# car.net
KiCad netlist of a schematic drawn in EAGLE
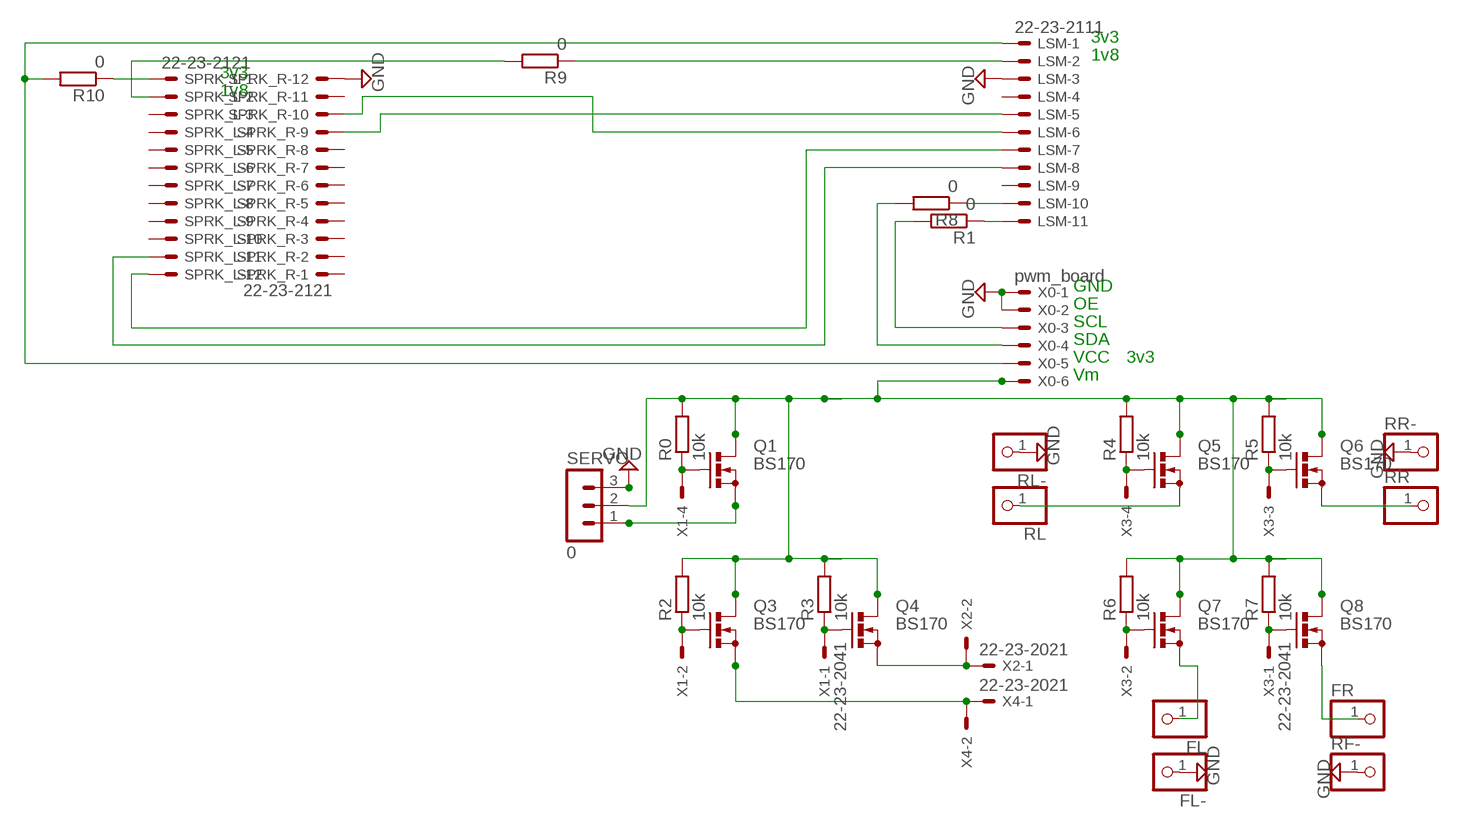
[diagram p0: schematic, sheet 1]

(export (version "E")
  (design (tool "Eeschema 10.0.6"))
  (components
    (comp (ref "FL")
      (value "PINHD-1X1")
      (footprint "eagle-import:1X01")
      (libsource (lib "eagle-import") (part "PINHD-1X1"))
    )
    (comp (ref "FL-")
      (value "PINHD-1X1")
      (footprint "eagle-import:1X01")
      (libsource (lib "eagle-import") (part "PINHD-1X1"))
    )
    (comp (ref "FR")
      (value "PINHD-1X1")
      (footprint "eagle-import:1X01")
      (libsource (lib "eagle-import") (part "PINHD-1X1"))
    )
    (comp (ref "LSM")
      (value "22-23-2111")
      (footprint "eagle-import:22-23-2111")
      (fields (field (name "MF") "MOLEX"))
      (libsource (lib "eagle-import") (part "22-23-2111"))
    )
    (comp (ref "Q1")
      (value "BS170")
      (footprint "eagle-import:SOT54E")
      (libsource (lib "eagle-import") (part "BS170"))
    )
    (comp (ref "Q3")
      (value "BS170")
      (footprint "eagle-import:SOT54E")
      (libsource (lib "eagle-import") (part "BS170"))
    )
    (comp (ref "Q4")
      (value "BS170")
      (footprint "eagle-import:SOT54E")
      (libsource (lib "eagle-import") (part "BS170"))
    )
    (comp (ref "Q5")
      (value "BS170")
      (footprint "eagle-import:SOT54E")
      (libsource (lib "eagle-import") (part "BS170"))
    )
    (comp (ref "Q6")
      (value "BS170")
      (footprint "eagle-import:SOT54E")
      (libsource (lib "eagle-import") (part "BS170"))
    )
    (comp (ref "Q7")
      (value "BS170")
      (footprint "eagle-import:SOT54E")
      (libsource (lib "eagle-import") (part "BS170"))
    )
    (comp (ref "Q8")
      (value "BS170")
      (footprint "eagle-import:SOT54E")
      (libsource (lib "eagle-import") (part "BS170"))
    )
    (comp (ref "R0")
      (value "10k")
      (footprint "eagle-import:0207_10")
      (libsource (lib "eagle-import") (part "R-EU_0207/10"))
    )
    (comp (ref "R1")
      (value "0")
      (footprint "eagle-import:0207_10")
      (libsource (lib "eagle-import") (part "R-EU_0207/10"))
    )
    (comp (ref "R2")
      (value "10k")
      (footprint "eagle-import:0207_10")
      (libsource (lib "eagle-import") (part "R-EU_0207/10"))
    )
    (comp (ref "R3")
      (value "10k")
      (footprint "eagle-import:0207_10")
      (libsource (lib "eagle-import") (part "R-EU_0207/10"))
    )
    (comp (ref "R4")
      (value "10k")
      (footprint "eagle-import:0207_10")
      (libsource (lib "eagle-import") (part "R-EU_0207/10"))
    )
    (comp (ref "R5")
      (value "10k")
      (footprint "eagle-import:0207_10")
      (libsource (lib "eagle-import") (part "R-EU_0207/10"))
    )
    (comp (ref "R6")
      (value "10k")
      (footprint "eagle-import:0207_10")
      (libsource (lib "eagle-import") (part "R-EU_0207/10"))
    )
    (comp (ref "R7")
      (value "10k")
      (footprint "eagle-import:0207_10")
      (libsource (lib "eagle-import") (part "R-EU_0207/10"))
    )
    (comp (ref "R8")
      (value "0")
      (footprint "eagle-import:0207_10")
      (libsource (lib "eagle-import") (part "R-EU_0207/10"))
    )
    (comp (ref "R9")
      (value "0")
      (footprint "eagle-import:0207_10")
      (libsource (lib "eagle-import") (part "R-EU_0207/10"))
    )
    (comp (ref "R10")
      (value "0")
      (footprint "eagle-import:0207_10")
      (libsource (lib "eagle-import") (part "R-EU_0207/10"))
    )
    (comp (ref "RF-")
      (value "PINHD-1X1")
      (footprint "eagle-import:1X01")
      (libsource (lib "eagle-import") (part "PINHD-1X1"))
    )
    (comp (ref "RL")
      (value "PINHD-1X1")
      (footprint "eagle-import:1X01")
      (libsource (lib "eagle-import") (part "PINHD-1X1"))
    )
    (comp (ref "RL-")
      (value "PINHD-1X1")
      (footprint "eagle-import:1X01")
      (libsource (lib "eagle-import") (part "PINHD-1X1"))
    )
    (comp (ref "RR")
      (value "PINHD-1X1")
      (footprint "eagle-import:1X01")
      (libsource (lib "eagle-import") (part "PINHD-1X1"))
    )
    (comp (ref "RR-")
      (value "PINHD-1X1")
      (footprint "eagle-import:1X01")
      (libsource (lib "eagle-import") (part "PINHD-1X1"))
    )
    (comp (ref "SERVO")
      (value "0")
      (footprint "eagle-import:MA03-1")
      (libsource (lib "eagle-import") (part "MA03-1"))
    )
    (comp (ref "SPRK_L")
      (value "22-23-2121")
      (footprint "eagle-import:22-23-2121")
      (fields (field (name "MF") "MOLEX"))
      (libsource (lib "eagle-import") (part "22-23-2121"))
    )
    (comp (ref "SPRK_R")
      (value "22-23-2121")
      (footprint "eagle-import:22-23-2121")
      (fields (field (name "MF") "MOLEX"))
      (libsource (lib "eagle-import") (part "22-23-2121"))
    )
    (comp (ref "X0")
      (value "pwm_board")
      (footprint "eagle-import:22-23-2061")
      (fields (field (name "MF") "MOLEX") (field (name "MPN") "22-23-2061"))
      (libsource (lib "eagle-import") (part "22-23-2061"))
    )
    (comp (ref "X1")
      (value "22-23-2041")
      (footprint "eagle-import:22-23-2041")
      (fields (field (name "MF") "MOLEX"))
      (libsource (lib "eagle-import") (part "22-23-2041"))
    )
    (comp (ref "X2")
      (value "22-23-2021")
      (footprint "eagle-import:22-23-2021")
      (fields (field (name "MF") "MOLEX"))
      (libsource (lib "eagle-import") (part "22-23-2021"))
    )
    (comp (ref "X3")
      (value "22-23-2041")
      (footprint "eagle-import:22-23-2041")
      (fields (field (name "MF") "MOLEX"))
      (libsource (lib "eagle-import") (part "22-23-2041"))
    )
    (comp (ref "X4")
      (value "22-23-2021")
      (footprint "eagle-import:22-23-2021")
      (fields (field (name "MF") "MOLEX"))
      (libsource (lib "eagle-import") (part "22-23-2021"))
    )
  )
  (nets
    (net (code "1") (name "GND") (class "Default")
      (node (ref "FL-") (pin "1") (pinfunction "1_1") (pintype "passive"))
      (node (ref "LSM") (pin "3") (pinfunction "S_3") (pintype "passive"))
      (node (ref "RF-") (pin "1") (pinfunction "1_1") (pintype "passive"))
      (node (ref "RL-") (pin "1") (pinfunction "1_1") (pintype "passive"))
      (node (ref "RR-") (pin "1") (pinfunction "1_1") (pintype "passive"))
      (node (ref "SERVO") (pin "3") (pinfunction "3_3") (pintype "passive"))
      (node (ref "SPRK_R") (pin "12") (pinfunction "S_12") (pintype "passive"))
      (node (ref "X0") (pin "1") (pinfunction "S_1") (pintype "passive"))
      (node (ref "X0") (pin "2") (pinfunction "S_2") (pintype "passive"))
    )
    (net (code "2") (name "Net-(FL-Pad1)") (class "Default")
      (node (ref "FL") (pin "1") (pinfunction "1_1") (pintype "passive"))
      (node (ref "Q7") (pin "S") (pinfunction "S_S") (pintype "passive"))
    )
    (net (code "3") (name "Net-(FR-Pad1)") (class "Default")
      (node (ref "FR") (pin "1") (pinfunction "1_1") (pintype "passive"))
      (node (ref "Q8") (pin "S") (pinfunction "S_S") (pintype "passive"))
    )
    (net (code "4") (name "Net-(LSMA-S)") (class "Default")
      (node (ref "LSM") (pin "1") (pinfunction "S_1") (pintype "passive"))
      (node (ref "R10") (pin "2") (pinfunction "2_2") (pintype "passive"))
      (node (ref "X0") (pin "5") (pinfunction "S_5") (pintype "passive"))
    )
    (net (code "5") (name "Net-(LSMB-S)") (class "Default")
      (node (ref "LSM") (pin "10") (pinfunction "S_10") (pintype "passive"))
      (node (ref "R8") (pin "1") (pinfunction "1_1") (pintype "passive"))
    )
    (net (code "6") (name "Net-(LSMC-S)") (class "Default")
      (node (ref "LSM") (pin "11") (pinfunction "S_11") (pintype "passive"))
      (node (ref "R1") (pin "1") (pinfunction "1_1") (pintype "passive"))
    )
    (net (code "7") (name "Net-(LSMD-S)") (class "Default")
      (node (ref "LSM") (pin "2") (pinfunction "S_2") (pintype "passive"))
      (node (ref "R9") (pin "1") (pinfunction "1_1") (pintype "passive"))
    )
    (net (code "8") (name "Net-(LSMG-S)") (class "Default")
      (node (ref "LSM") (pin "5") (pinfunction "S_5") (pintype "passive"))
      (node (ref "SPRK_R") (pin "9") (pinfunction "S_9") (pintype "passive"))
    )
    (net (code "9") (name "Net-(LSMH-S)") (class "Default")
      (node (ref "LSM") (pin "6") (pinfunction "S_6") (pintype "passive"))
      (node (ref "SPRK_R") (pin "10") (pinfunction "S_10") (pintype "passive"))
    )
    (net (code "10") (name "Net-(LSMI-S)") (class "Default")
      (node (ref "LSM") (pin "7") (pinfunction "S_7") (pintype "passive"))
      (node (ref "SPRK_L") (pin "12") (pinfunction "S_12") (pintype "passive"))
    )
    (net (code "11") (name "Net-(LSMJ-S)") (class "Default")
      (node (ref "LSM") (pin "8") (pinfunction "S_8") (pintype "passive"))
      (node (ref "SPRK_L") (pin "11") (pinfunction "S_11") (pintype "passive"))
    )
    (net (code "12") (name "Net-(Q1-PadS)") (class "Default")
      (node (ref "Q1") (pin "S") (pinfunction "S_S") (pintype "passive"))
      (node (ref "SERVO") (pin "1") (pinfunction "1_1") (pintype "passive"))
    )
    (net (code "13") (name "Net-(Q5-PadS)") (class "Default")
      (node (ref "Q5") (pin "S") (pinfunction "S_S") (pintype "passive"))
      (node (ref "RL") (pin "1") (pinfunction "1_1") (pintype "passive"))
    )
    (net (code "14") (name "Net-(Q6-PadS)") (class "Default")
      (node (ref "Q6") (pin "S") (pinfunction "S_S") (pintype "passive"))
      (node (ref "RR") (pin "1") (pinfunction "1_1") (pintype "passive"))
    )
    (net (code "15") (name "Net-(SPRK_LA-S)") (class "Default")
      (node (ref "R10") (pin "1") (pinfunction "1_1") (pintype "passive"))
      (node (ref "SPRK_L") (pin "1") (pinfunction "S_1") (pintype "passive"))
    )
    (net (code "16") (name "Net-(SPRK_LE-S)") (class "Default")
      (node (ref "R9") (pin "2") (pinfunction "2_2") (pintype "passive"))
      (node (ref "SPRK_L") (pin "2") (pinfunction "S_2") (pintype "passive"))
    )
    (net (code "17") (name "Net-(X0C-S)") (class "Default")
      (node (ref "R1") (pin "2") (pinfunction "2_2") (pintype "passive"))
      (node (ref "X0") (pin "3") (pinfunction "S_3") (pintype "passive"))
    )
    (net (code "18") (name "Net-(X0D-S)") (class "Default")
      (node (ref "R8") (pin "2") (pinfunction "2_2") (pintype "passive"))
      (node (ref "X0") (pin "4") (pinfunction "S_4") (pintype "passive"))
    )
    (net (code "19") (name "Net-(X0F-S)") (class "Default")
      (node (ref "Q1") (pin "D") (pinfunction "D_D") (pintype "passive"))
      (node (ref "Q3") (pin "D") (pinfunction "D_D") (pintype "passive"))
      (node (ref "Q4") (pin "D") (pinfunction "D_D") (pintype "passive"))
      (node (ref "Q5") (pin "D") (pinfunction "D_D") (pintype "passive"))
      (node (ref "Q6") (pin "D") (pinfunction "D_D") (pintype "passive"))
      (node (ref "Q7") (pin "D") (pinfunction "D_D") (pintype "passive"))
      (node (ref "Q8") (pin "D") (pinfunction "D_D") (pintype "passive"))
      (node (ref "R0") (pin "2") (pinfunction "2_2") (pintype "passive"))
      (node (ref "R2") (pin "2") (pinfunction "2_2") (pintype "passive"))
      (node (ref "R3") (pin "2") (pinfunction "2_2") (pintype "passive"))
      (node (ref "R4") (pin "2") (pinfunction "2_2") (pintype "passive"))
      (node (ref "R5") (pin "2") (pinfunction "2_2") (pintype "passive"))
      (node (ref "R6") (pin "2") (pinfunction "2_2") (pintype "passive"))
      (node (ref "R7") (pin "2") (pinfunction "2_2") (pintype "passive"))
      (node (ref "SERVO") (pin "2") (pinfunction "2_2") (pintype "passive"))
      (node (ref "X0") (pin "6") (pinfunction "S_6") (pintype "passive"))
    )
    (net (code "20") (name "Net-(X1A-S)") (class "Default")
      (node (ref "Q4") (pin "G") (pinfunction "G_G") (pintype "passive"))
      (node (ref "R3") (pin "1") (pinfunction "1_1") (pintype "passive"))
      (node (ref "X1") (pin "1") (pinfunction "S_1") (pintype "passive"))
    )
    (net (code "21") (name "Net-(X1B-S)") (class "Default")
      (node (ref "Q3") (pin "G") (pinfunction "G_G") (pintype "passive"))
      (node (ref "R2") (pin "1") (pinfunction "1_1") (pintype "passive"))
      (node (ref "X1") (pin "2") (pinfunction "S_2") (pintype "passive"))
    )
    (net (code "22") (name "Net-(X1D-S)") (class "Default")
      (node (ref "Q1") (pin "G") (pinfunction "G_G") (pintype "passive"))
      (node (ref "R0") (pin "1") (pinfunction "1_1") (pintype "passive"))
      (node (ref "X1") (pin "4") (pinfunction "S_4") (pintype "passive"))
    )
    (net (code "23") (name "Net-(X2A-S)") (class "Default")
      (node (ref "Q4") (pin "S") (pinfunction "S_S") (pintype "passive"))
      (node (ref "X2") (pin "1") (pinfunction "S_1") (pintype "passive"))
      (node (ref "X2") (pin "2") (pinfunction "S_2") (pintype "passive"))
    )
    (net (code "24") (name "Net-(X3A-S)") (class "Default")
      (node (ref "Q8") (pin "G") (pinfunction "G_G") (pintype "passive"))
      (node (ref "R7") (pin "1") (pinfunction "1_1") (pintype "passive"))
      (node (ref "X3") (pin "1") (pinfunction "S_1") (pintype "passive"))
    )
    (net (code "25") (name "Net-(X3B-S)") (class "Default")
      (node (ref "Q7") (pin "G") (pinfunction "G_G") (pintype "passive"))
      (node (ref "R6") (pin "1") (pinfunction "1_1") (pintype "passive"))
      (node (ref "X3") (pin "2") (pinfunction "S_2") (pintype "passive"))
    )
    (net (code "26") (name "Net-(X3C-S)") (class "Default")
      (node (ref "Q6") (pin "G") (pinfunction "G_G") (pintype "passive"))
      (node (ref "R5") (pin "1") (pinfunction "1_1") (pintype "passive"))
      (node (ref "X3") (pin "3") (pinfunction "S_3") (pintype "passive"))
    )
    (net (code "27") (name "Net-(X3D-S)") (class "Default")
      (node (ref "Q5") (pin "G") (pinfunction "G_G") (pintype "passive"))
      (node (ref "R4") (pin "1") (pinfunction "1_1") (pintype "passive"))
      (node (ref "X3") (pin "4") (pinfunction "S_4") (pintype "passive"))
    )
    (net (code "28") (name "Net-(X4A-S)") (class "Default")
      (node (ref "Q3") (pin "S") (pinfunction "S_S") (pintype "passive"))
      (node (ref "X4") (pin "1") (pinfunction "S_1") (pintype "passive"))
      (node (ref "X4") (pin "2") (pinfunction "S_2") (pintype "passive"))
    )
    (net (code "29") (name "unconnected-(LSMF-S-Pad4)") (class "Default")
      (node (ref "LSM") (pin "4") (pinfunction "S_4") (pintype "passive"))
    )
    (net (code "30") (name "unconnected-(LSMK-S-Pad9)") (class "Default")
      (node (ref "LSM") (pin "9") (pinfunction "S_9") (pintype "passive"))
    )
    (net (code "31") (name "unconnected-(SPRK_LB-S-Pad10)") (class "Default")
      (node (ref "SPRK_L") (pin "10") (pinfunction "S_10") (pintype "passive"))
    )
    (net (code "32") (name "unconnected-(SPRK_LF-S-Pad3)") (class "Default")
      (node (ref "SPRK_L") (pin "3") (pinfunction "S_3") (pintype "passive"))
    )
    (net (code "33") (name "unconnected-(SPRK_LG-S-Pad4)") (class "Default")
      (node (ref "SPRK_L") (pin "4") (pinfunction "S_4") (pintype "passive"))
    )
    (net (code "34") (name "unconnected-(SPRK_LH-S-Pad5)") (class "Default")
      (node (ref "SPRK_L") (pin "5") (pinfunction "S_5") (pintype "passive"))
    )
    (net (code "35") (name "unconnected-(SPRK_LI-S-Pad6)") (class "Default")
      (node (ref "SPRK_L") (pin "6") (pinfunction "S_6") (pintype "passive"))
    )
    (net (code "36") (name "unconnected-(SPRK_LJ-S-Pad7)") (class "Default")
      (node (ref "SPRK_L") (pin "7") (pinfunction "S_7") (pintype "passive"))
    )
    (net (code "37") (name "unconnected-(SPRK_LK-S-Pad8)") (class "Default")
      (node (ref "SPRK_L") (pin "8") (pinfunction "S_8") (pintype "passive"))
    )
    (net (code "38") (name "unconnected-(SPRK_LL-S-Pad9)") (class "Default")
      (node (ref "SPRK_L") (pin "9") (pinfunction "S_9") (pintype "passive"))
    )
    (net (code "39") (name "unconnected-(SPRK_RA-S-Pad1)") (class "Default")
      (node (ref "SPRK_R") (pin "1") (pinfunction "S_1") (pintype "passive"))
    )
    (net (code "40") (name "unconnected-(SPRK_RC-S-Pad11)") (class "Default")
      (node (ref "SPRK_R") (pin "11") (pinfunction "S_11") (pintype "passive"))
    )
    (net (code "41") (name "unconnected-(SPRK_RE-S-Pad2)") (class "Default")
      (node (ref "SPRK_R") (pin "2") (pinfunction "S_2") (pintype "passive"))
    )
    (net (code "42") (name "unconnected-(SPRK_RF-S-Pad3)") (class "Default")
      (node (ref "SPRK_R") (pin "3") (pinfunction "S_3") (pintype "passive"))
    )
    (net (code "43") (name "unconnected-(SPRK_RG-S-Pad4)") (class "Default")
      (node (ref "SPRK_R") (pin "4") (pinfunction "S_4") (pintype "passive"))
    )
    (net (code "44") (name "unconnected-(SPRK_RH-S-Pad5)") (class "Default")
      (node (ref "SPRK_R") (pin "5") (pinfunction "S_5") (pintype "passive"))
    )
    (net (code "45") (name "unconnected-(SPRK_RI-S-Pad6)") (class "Default")
      (node (ref "SPRK_R") (pin "6") (pinfunction "S_6") (pintype "passive"))
    )
    (net (code "46") (name "unconnected-(SPRK_RJ-S-Pad7)") (class "Default")
      (node (ref "SPRK_R") (pin "7") (pinfunction "S_7") (pintype "passive"))
    )
    (net (code "47") (name "unconnected-(SPRK_RK-S-Pad8)") (class "Default")
      (node (ref "SPRK_R") (pin "8") (pinfunction "S_8") (pintype "passive"))
    )
  )
)
